# Schematics.net
KiCad netlist of a schematic drawn in EAGLE
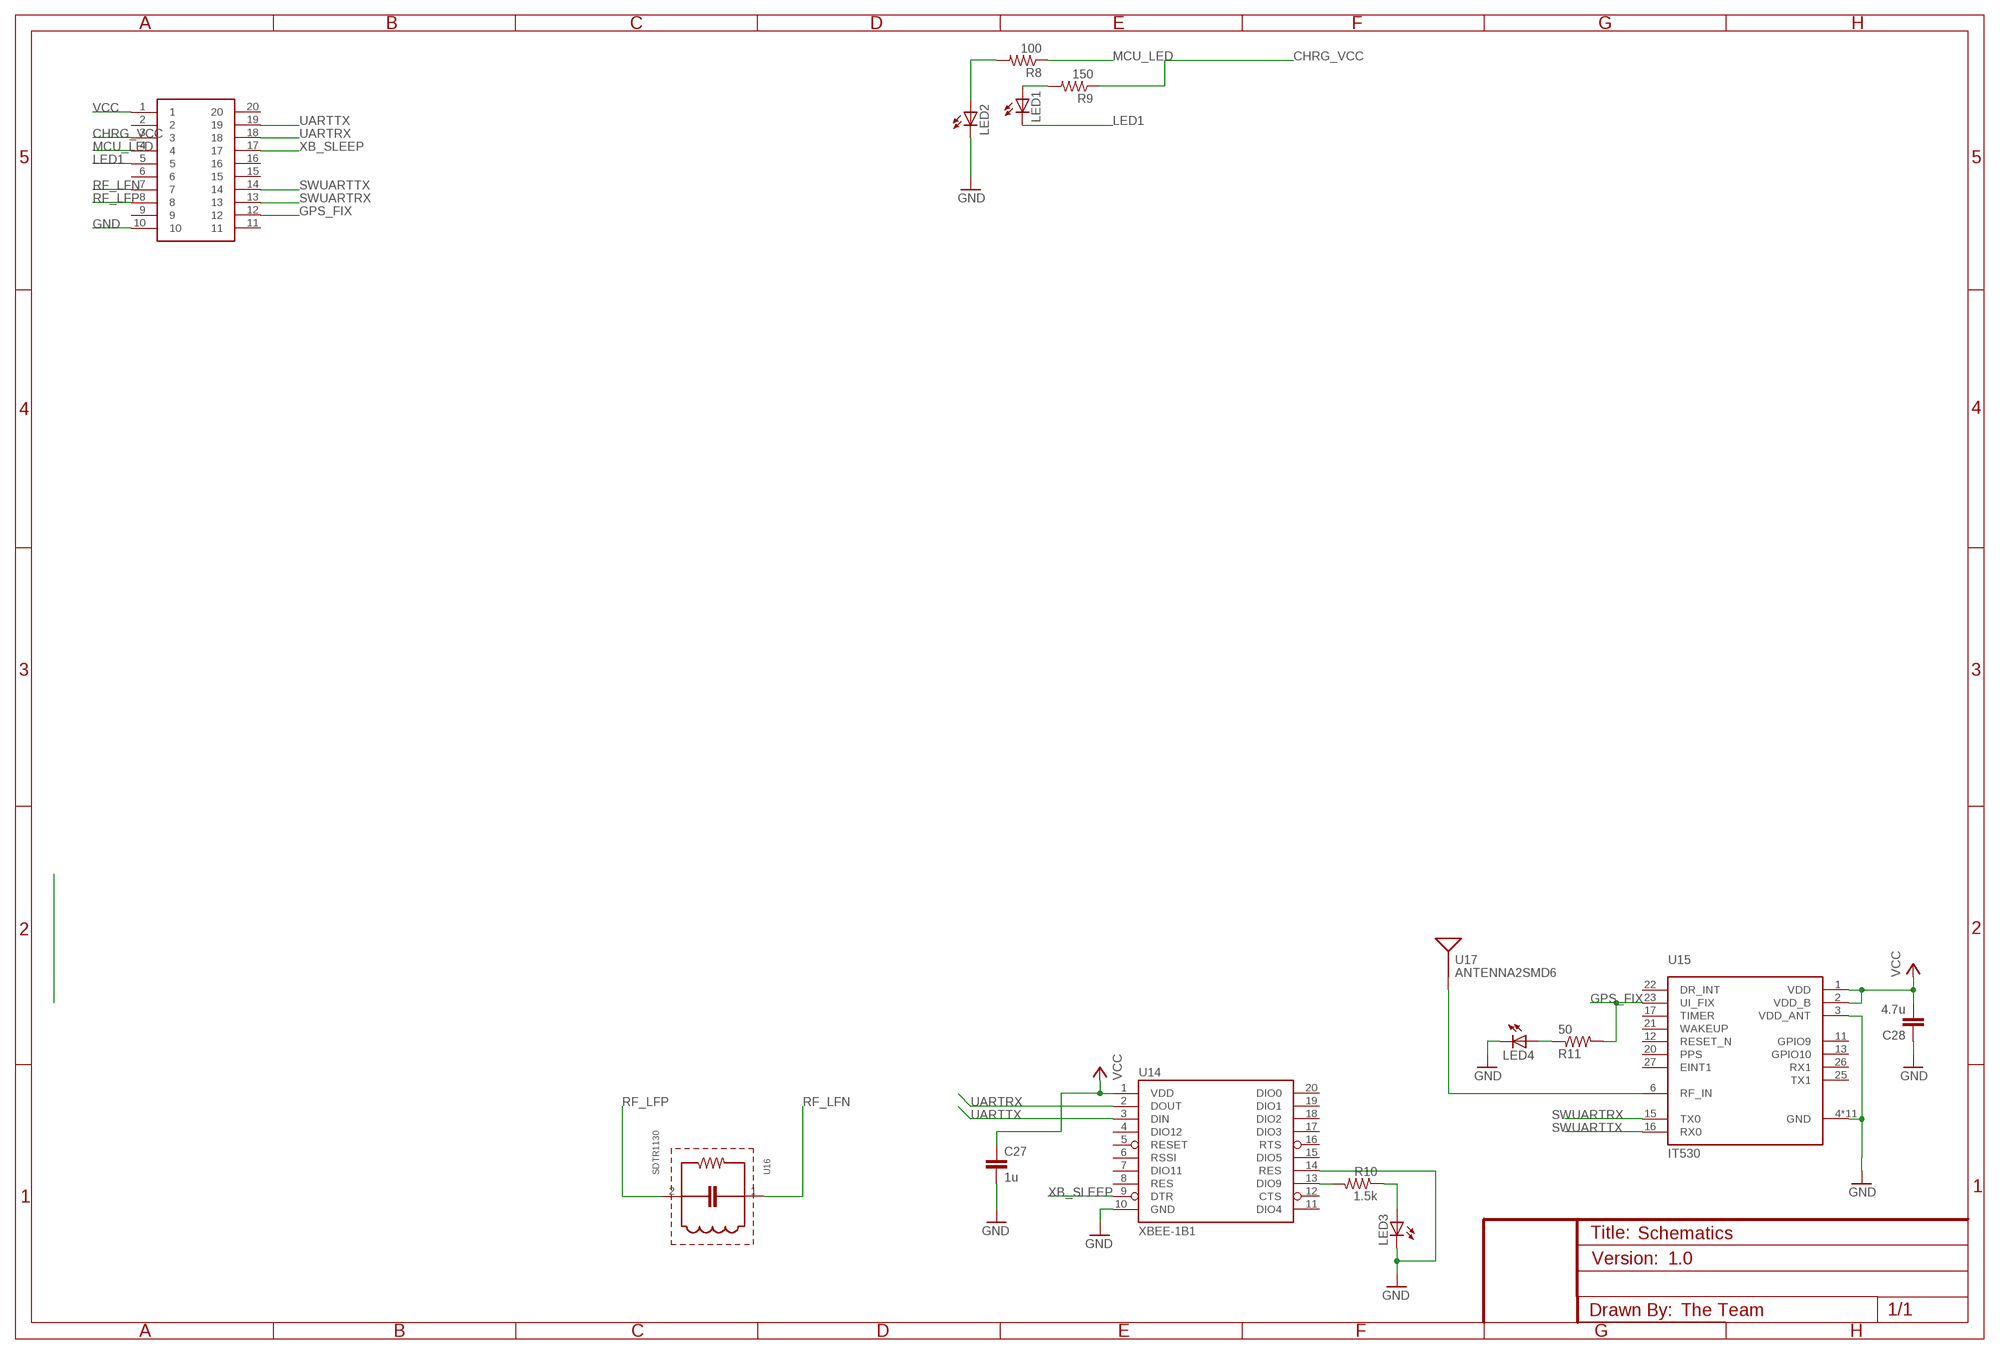
[diagram p0: schematic, sheet 1]

(export (version "E")
  (design (tool "Eeschema 10.0.6"))
  (components
    (comp (ref "C27")
      (value "1u")
      (footprint "eagle-import:C0603")
      (libsource (lib "eagle-import") (part "C-EUC0603"))
    )
    (comp (ref "C28")
      (value "4.7u")
      (footprint "eagle-import:C0603")
      (libsource (lib "eagle-import") (part "C-EUC0603"))
    )
    (comp (ref "JP4")
      (value "20-HEAD")
      (footprint "eagle-import:20-HEAD")
      (libsource (lib "eagle-import") (part "20-HEAD"))
    )
    (comp (ref "LED1")
      (value "LED")
      (footprint "eagle-import:SMARTLED-TTW")
      (libsource (lib "eagle-import") (part "LED"))
    )
    (comp (ref "LED2")
      (value "LED")
      (footprint "eagle-import:SMARTLED-TTW")
      (libsource (lib "eagle-import") (part "LED"))
    )
    (comp (ref "LED3")
      (value "LED")
      (footprint "eagle-import:SMARTLED-TTW")
      (libsource (lib "eagle-import") (part "LED"))
    )
    (comp (ref "LED4")
      (value "LED")
      (footprint "eagle-import:SMARTLED-TTW")
      (libsource (lib "eagle-import") (part "LED"))
    )
    (comp (ref "R8")
      (value "100")
      (footprint "eagle-import:R0603")
      (libsource (lib "eagle-import") (part "R-US_R0603"))
    )
    (comp (ref "R9")
      (value "150")
      (footprint "eagle-import:R0603")
      (libsource (lib "eagle-import") (part "R-US_R0603"))
    )
    (comp (ref "R10")
      (value "1.5k")
      (footprint "eagle-import:R0603")
      (libsource (lib "eagle-import") (part "R-US_R0603"))
    )
    (comp (ref "R11")
      (value "50")
      (footprint "eagle-import:R0603")
      (libsource (lib "eagle-import") (part "R-US_R0603"))
    )
    (comp (ref "U14")
      (value "XBEE-1B1")
      (footprint "eagle-import:XBEE-1")
      (libsource (lib "eagle-import") (part "XBEE-1B1"))
    )
    (comp (ref "U15")
      (value "IT530")
      (footprint "eagle-import:IT530")
      (libsource (lib "eagle-import") (part "IT530"))
    )
    (comp (ref "U16")
      (value "SDTR1130")
      (footprint "eagle-import:SDTR1130-SMD")
      (libsource (lib "eagle-import") (part "SDTR1130"))
    )
    (comp (ref "U17")
      (value "ANTENNA2SMD6")
      (footprint "eagle-import:ANTENNA-CHIP6")
      (libsource (lib "eagle-import") (part "ANTENNA2SMD6"))
    )
  )
  (nets
    (net (code "1") (name "/CHRG_VCC") (class "Default")
      (node (ref "JP4") (pin "3") (pinfunction "3_3") (pintype "bidirectional"))
      (node (ref "R9") (pin "1") (pinfunction "1_1") (pintype "passive"))
    )
    (net (code "2") (name "/GPS_FIX") (class "Default")
      (node (ref "JP4") (pin "12") (pinfunction "12_12") (pintype "bidirectional"))
      (node (ref "R11") (pin "2") (pinfunction "2_2") (pintype "passive"))
      (node (ref "U15") (pin "23") (pinfunction "UI_FIX_23") (pintype "bidirectional"))
    )
    (net (code "3") (name "/LED1") (class "Default")
      (node (ref "JP4") (pin "5") (pinfunction "5_5") (pintype "bidirectional"))
      (node (ref "LED1") (pin "C@1") (pinfunction "C_C@1") (pintype "passive"))
    )
    (net (code "4") (name "/MCU_LED") (class "Default")
      (node (ref "JP4") (pin "4") (pinfunction "4_4") (pintype "bidirectional"))
      (node (ref "R8") (pin "1") (pinfunction "1_1") (pintype "passive"))
    )
    (net (code "5") (name "/RF_LFN") (class "Default")
      (node (ref "JP4") (pin "7") (pinfunction "7_7") (pintype "bidirectional"))
      (node (ref "U16") (pin "1") (pinfunction "1_1") (pintype "bidirectional"))
    )
    (net (code "6") (name "/RF_LFP") (class "Default")
      (node (ref "JP4") (pin "8") (pinfunction "8_8") (pintype "bidirectional"))
      (node (ref "U16") (pin "2") (pinfunction "2_2") (pintype "bidirectional"))
    )
    (net (code "7") (name "/SWUARTRX") (class "Default")
      (node (ref "JP4") (pin "13") (pinfunction "13_13") (pintype "bidirectional"))
      (node (ref "U15") (pin "15") (pinfunction "TX0_15") (pintype "bidirectional"))
    )
    (net (code "8") (name "/SWUARTTX") (class "Default")
      (node (ref "JP4") (pin "14") (pinfunction "14_14") (pintype "bidirectional"))
      (node (ref "U15") (pin "16") (pinfunction "RX0_16") (pintype "bidirectional"))
    )
    (net (code "9") (name "/UARTRX") (class "Default")
      (node (ref "JP4") (pin "18") (pinfunction "18_18") (pintype "bidirectional"))
      (node (ref "U14") (pin "2") (pinfunction "DOUT_2") (pintype "output"))
    )
    (net (code "10") (name "/UARTTX") (class "Default")
      (node (ref "JP4") (pin "19") (pinfunction "19_19") (pintype "bidirectional"))
      (node (ref "U14") (pin "3") (pinfunction "DIN_3") (pintype "input"))
    )
    (net (code "11") (name "/XB_SLEEP") (class "Default")
      (node (ref "JP4") (pin "17") (pinfunction "17_17") (pintype "bidirectional"))
      (node (ref "U14") (pin "9") (pinfunction "DTR_9") (pintype "bidirectional"))
    )
    (net (code "12") (name "GND") (class "Default")
      (node (ref "C27") (pin "2") (pinfunction "2_2") (pintype "passive"))
      (node (ref "C28") (pin "1") (pinfunction "1_1") (pintype "passive"))
      (node (ref "JP4") (pin "10") (pinfunction "10_10") (pintype "bidirectional"))
      (node (ref "LED2") (pin "C@1") (pinfunction "C_C@1") (pintype "passive"))
      (node (ref "LED3") (pin "C@1") (pinfunction "C_C@1") (pintype "passive"))
      (node (ref "LED4") (pin "C@1") (pinfunction "C_C@1") (pintype "passive"))
      (node (ref "U14") (pin "10") (pinfunction "GND_10") (pintype "power_in"))
      (node (ref "U14") (pin "14") (pinfunction "RES_14") (pintype "bidirectional"))
      (node (ref "U15") (pin "10") (pinfunction "GND_10") (pintype "bidirectional"))
      (node (ref "U15") (pin "14") (pinfunction "GND_14") (pintype "bidirectional"))
      (node (ref "U15") (pin "18") (pinfunction "GND_18") (pintype "bidirectional"))
      (node (ref "U15") (pin "19") (pinfunction "GND_19") (pintype "bidirectional"))
      (node (ref "U15") (pin "24") (pinfunction "GND_24") (pintype "bidirectional"))
      (node (ref "U15") (pin "28") (pinfunction "GND_28") (pintype "bidirectional"))
      (node (ref "U15") (pin "3") (pinfunction "VDD_ANT_3") (pintype "bidirectional"))
      (node (ref "U15") (pin "4") (pinfunction "GND_4") (pintype "bidirectional"))
      (node (ref "U15") (pin "5") (pinfunction "GND_5") (pintype "bidirectional"))
      (node (ref "U15") (pin "7") (pinfunction "GND_7") (pintype "bidirectional"))
      (node (ref "U15") (pin "8") (pinfunction "GND_8") (pintype "bidirectional"))
      (node (ref "U15") (pin "9") (pinfunction "GND_9") (pintype "bidirectional"))
    )
    (net (code "13") (name "Net-(LED1-A)") (class "Default")
      (node (ref "LED1") (pin "A@1") (pinfunction "A_A@1") (pintype "passive"))
      (node (ref "R9") (pin "2") (pinfunction "2_2") (pintype "passive"))
    )
    (net (code "14") (name "Net-(LED2-A)") (class "Default")
      (node (ref "LED2") (pin "A@1") (pinfunction "A_A@1") (pintype "passive"))
      (node (ref "R8") (pin "2") (pinfunction "2_2") (pintype "passive"))
    )
    (net (code "15") (name "Net-(LED3-A)") (class "Default")
      (node (ref "LED3") (pin "A@1") (pinfunction "A_A@1") (pintype "passive"))
      (node (ref "R10") (pin "1") (pinfunction "1_1") (pintype "passive"))
    )
    (net (code "16") (name "Net-(LED4-A)") (class "Default")
      (node (ref "LED4") (pin "A@1") (pinfunction "A_A@1") (pintype "passive"))
      (node (ref "R11") (pin "1") (pinfunction "1_1") (pintype "passive"))
    )
    (net (code "17") (name "Net-(U14-DIO9)") (class "Default")
      (node (ref "R10") (pin "2") (pinfunction "2_2") (pintype "passive"))
      (node (ref "U14") (pin "13") (pinfunction "DIO9_13") (pintype "bidirectional"))
    )
    (net (code "18") (name "Net-(U15-RF_IN)") (class "Default")
      (node (ref "U15") (pin "6") (pinfunction "RF_IN_6") (pintype "bidirectional"))
      (node (ref "U17") (pin "1") (pinfunction "SIGNAL_1") (pintype "bidirectional"))
    )
    (net (code "19") (name "VCC") (class "Default")
      (node (ref "C27") (pin "1") (pinfunction "1_1") (pintype "passive"))
      (node (ref "C28") (pin "2") (pinfunction "2_2") (pintype "passive"))
      (node (ref "JP4") (pin "1") (pinfunction "1_1") (pintype "bidirectional"))
      (node (ref "U14") (pin "1") (pinfunction "VDD_1") (pintype "power_in"))
      (node (ref "U15") (pin "1") (pinfunction "VDD_1") (pintype "bidirectional"))
      (node (ref "U15") (pin "2") (pinfunction "VDD_B_2") (pintype "bidirectional"))
    )
    (net (code "20") (name "unconnected-(JP4-Pad2)") (class "Default")
      (node (ref "JP4") (pin "2") (pinfunction "2_2") (pintype "bidirectional"))
    )
    (net (code "21") (name "unconnected-(JP4-Pad6)") (class "Default")
      (node (ref "JP4") (pin "6") (pinfunction "6_6") (pintype "bidirectional"))
    )
    (net (code "22") (name "unconnected-(JP4-Pad9)") (class "Default")
      (node (ref "JP4") (pin "9") (pinfunction "9_9") (pintype "bidirectional"))
    )
    (net (code "23") (name "unconnected-(JP4-Pad11)") (class "Default")
      (node (ref "JP4") (pin "11") (pinfunction "11_11") (pintype "bidirectional"))
    )
    (net (code "24") (name "unconnected-(JP4-Pad15)") (class "Default")
      (node (ref "JP4") (pin "15") (pinfunction "15_15") (pintype "bidirectional"))
    )
    (net (code "25") (name "unconnected-(JP4-Pad16)") (class "Default")
      (node (ref "JP4") (pin "16") (pinfunction "16_16") (pintype "bidirectional"))
    )
    (net (code "26") (name "unconnected-(JP4-Pad20)") (class "Default")
      (node (ref "JP4") (pin "20") (pinfunction "20_20") (pintype "bidirectional"))
    )
    (net (code "27") (name "unconnected-(U14-CTS-Pad12)") (class "Default")
      (node (ref "U14") (pin "12") (pinfunction "CTS_12") (pintype "output"))
    )
    (net (code "28") (name "unconnected-(U14-DIO0-Pad20)") (class "Default")
      (node (ref "U14") (pin "20") (pinfunction "DIO0_20") (pintype "bidirectional"))
    )
    (net (code "29") (name "unconnected-(U14-DIO1-Pad19)") (class "Default")
      (node (ref "U14") (pin "19") (pinfunction "DIO1_19") (pintype "bidirectional"))
    )
    (net (code "30") (name "unconnected-(U14-DIO2-Pad18)") (class "Default")
      (node (ref "U14") (pin "18") (pinfunction "DIO2_18") (pintype "bidirectional"))
    )
    (net (code "31") (name "unconnected-(U14-DIO3-Pad17)") (class "Default")
      (node (ref "U14") (pin "17") (pinfunction "DIO3_17") (pintype "bidirectional"))
    )
    (net (code "32") (name "unconnected-(U14-DIO4-Pad11)") (class "Default")
      (node (ref "U14") (pin "11") (pinfunction "DIO4_11") (pintype "bidirectional"))
    )
    (net (code "33") (name "unconnected-(U14-DIO5-Pad15)") (class "Default")
      (node (ref "U14") (pin "15") (pinfunction "DIO5_15") (pintype "bidirectional"))
    )
    (net (code "34") (name "unconnected-(U14-DIO11-Pad7)") (class "Default")
      (node (ref "U14") (pin "7") (pinfunction "DIO11_7") (pintype "bidirectional"))
    )
    (net (code "35") (name "unconnected-(U14-DIO12-Pad4)") (class "Default")
      (node (ref "U14") (pin "4") (pinfunction "DIO12_4") (pintype "bidirectional"))
    )
    (net (code "36") (name "unconnected-(U14-RES-Pad8)") (class "Default")
      (node (ref "U14") (pin "8") (pinfunction "RES_8") (pintype "bidirectional"))
    )
    (net (code "37") (name "unconnected-(U14-RESET-Pad5)") (class "Default")
      (node (ref "U14") (pin "5") (pinfunction "RESET_5") (pintype "input"))
    )
    (net (code "38") (name "unconnected-(U14-RSSI-Pad6)") (class "Default")
      (node (ref "U14") (pin "6") (pinfunction "RSSI_6") (pintype "bidirectional"))
    )
    (net (code "39") (name "unconnected-(U14-RTS-Pad16)") (class "Default")
      (node (ref "U14") (pin "16") (pinfunction "RTS_16") (pintype "input"))
    )
    (net (code "40") (name "unconnected-(U15-DR_INT-Pad22)") (class "Default")
      (node (ref "U15") (pin "22") (pinfunction "DR_INT_22") (pintype "bidirectional"))
    )
    (net (code "41") (name "unconnected-(U15-EINT1-Pad27)") (class "Default")
      (node (ref "U15") (pin "27") (pinfunction "EINT1_27") (pintype "bidirectional"))
    )
    (net (code "42") (name "unconnected-(U15-GPIO9-Pad11)") (class "Default")
      (node (ref "U15") (pin "11") (pinfunction "GPIO9_11") (pintype "bidirectional"))
    )
    (net (code "43") (name "unconnected-(U15-GPIO10-Pad13)") (class "Default")
      (node (ref "U15") (pin "13") (pinfunction "GPIO10_13") (pintype "bidirectional"))
    )
    (net (code "44") (name "unconnected-(U15-PPS-Pad20)") (class "Default")
      (node (ref "U15") (pin "20") (pinfunction "PPS_20") (pintype "bidirectional"))
    )
    (net (code "45") (name "unconnected-(U15-RESET_N-Pad12)") (class "Default")
      (node (ref "U15") (pin "12") (pinfunction "RESET_N_12") (pintype "bidirectional"))
    )
    (net (code "46") (name "unconnected-(U15-RX1-Pad26)") (class "Default")
      (node (ref "U15") (pin "26") (pinfunction "RX1_26") (pintype "bidirectional"))
    )
    (net (code "47") (name "unconnected-(U15-TIMER-Pad17)") (class "Default")
      (node (ref "U15") (pin "17") (pinfunction "TIMER_17") (pintype "bidirectional"))
    )
    (net (code "48") (name "unconnected-(U15-TX1-Pad25)") (class "Default")
      (node (ref "U15") (pin "25") (pinfunction "TX1_25") (pintype "bidirectional"))
    )
    (net (code "49") (name "unconnected-(U15-WAKEUP-Pad21)") (class "Default")
      (node (ref "U15") (pin "21") (pinfunction "WAKEUP_21") (pintype "bidirectional"))
    )
  )
)
